# CONN.net
KiCad netlist of a schematic drawn in Altium Designer
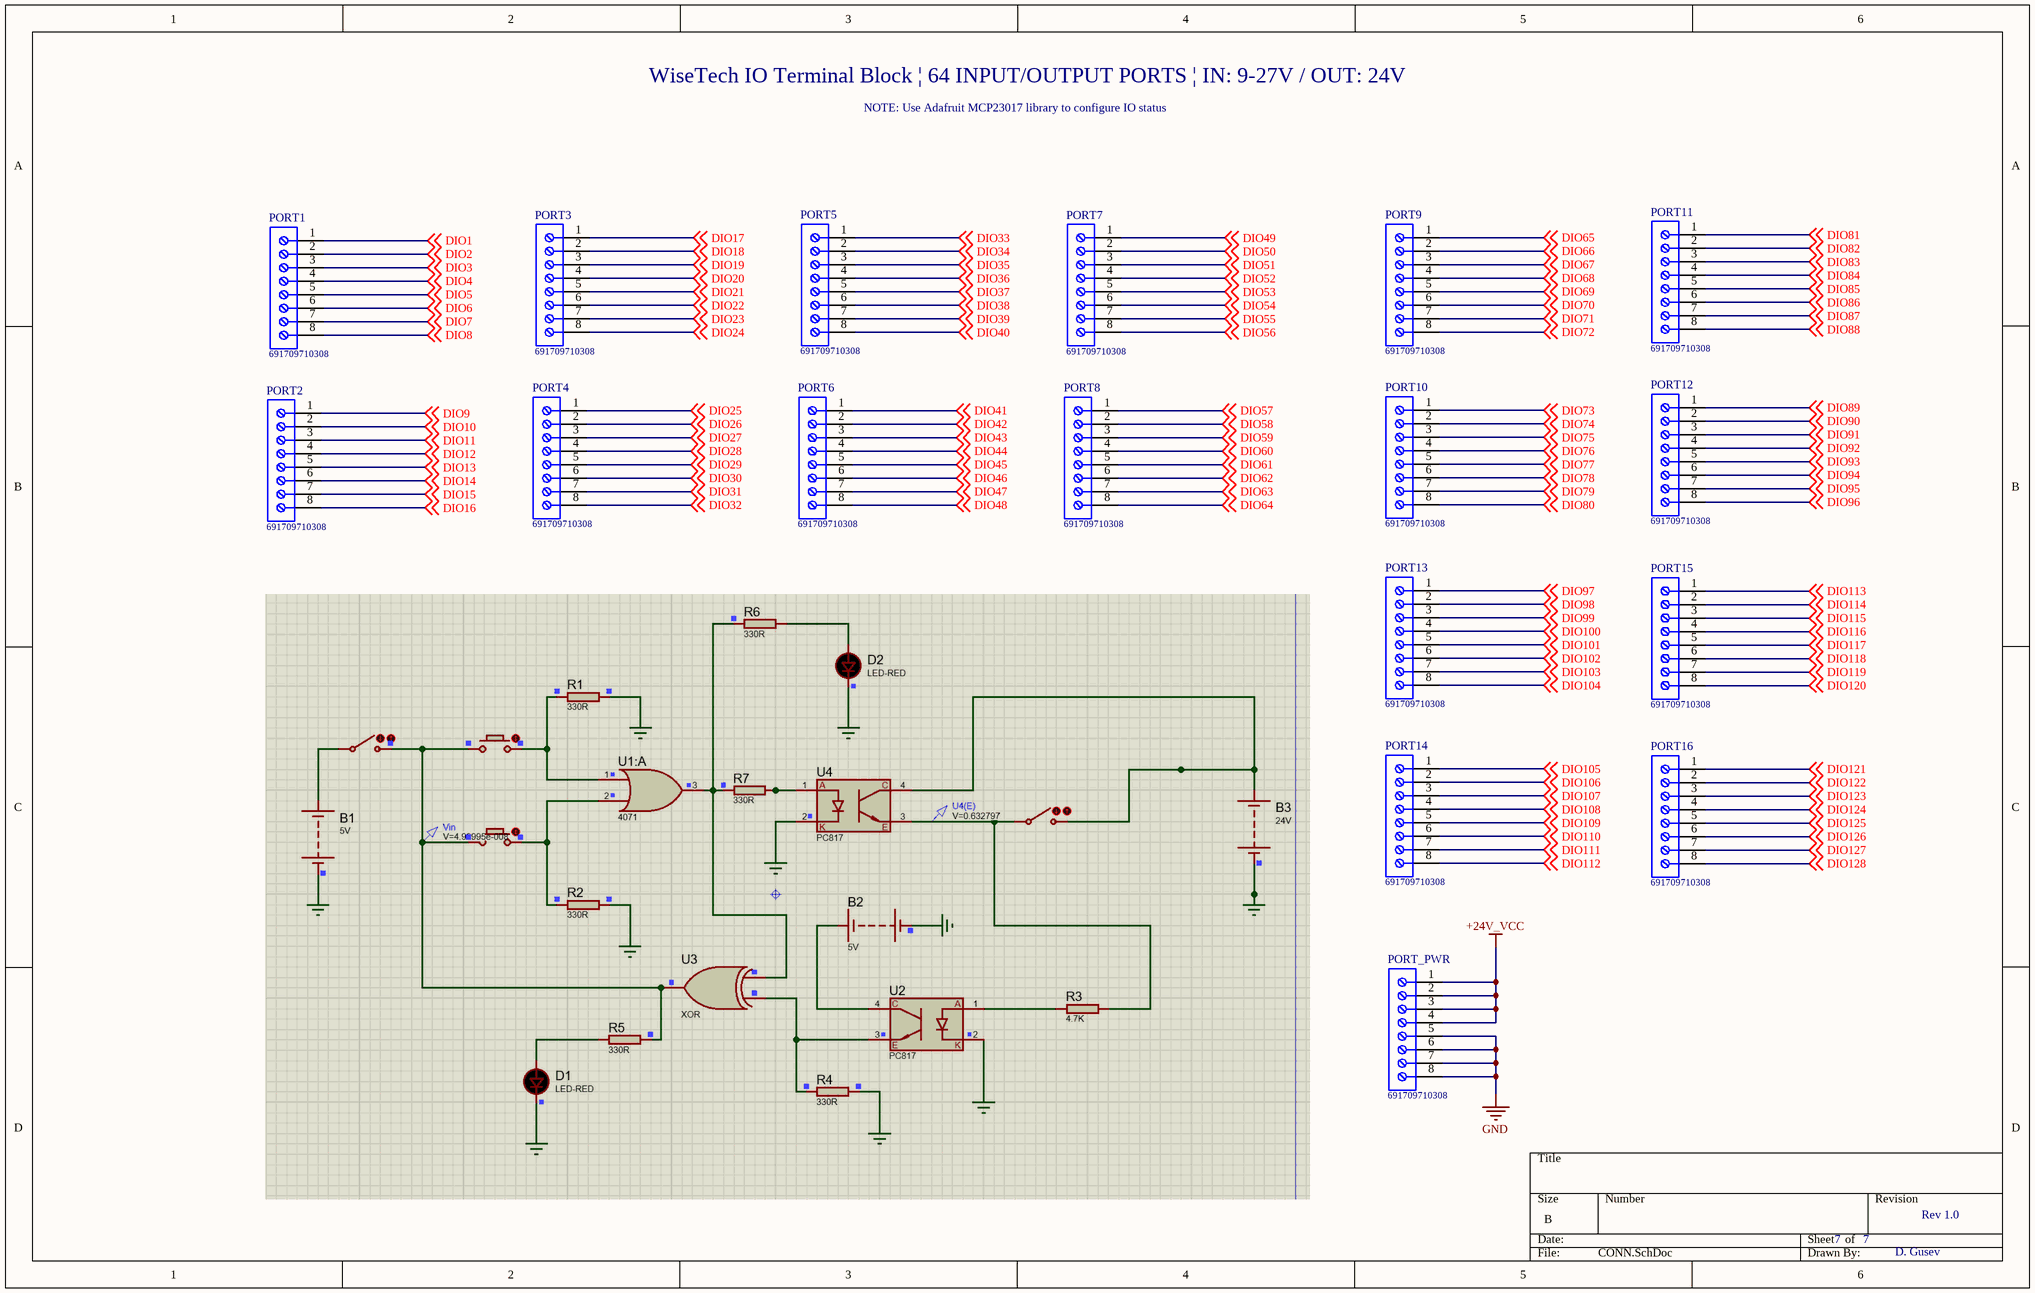
[diagram p0: CONN.SchDoc]

(export (version "E")
  (design (tool "Eeschema 10.0.6"))
  (components
    (comp (ref "PORT1")
      (value "691709710308")
      (footprint "691709710308")
      (description "Serie 7097 - 5.00 mm Horizontal Entry SMT with Pressure Clamp WR-TBL, 8 pin")
      (fields (field (name "MANUFACTURER") "Wurth Elektronik") (field (name "PUBLISHER") "WurthElektronik"))
      (libsource (lib "") (part "WE-CN-1P-F-TB8_2"))
    )
    (comp (ref "PORT2")
      (value "691709710308")
      (footprint "691709710308")
      (description "Serie 7097 - 5.00 mm Horizontal Entry SMT with Pressure Clamp WR-TBL, 8 pin")
      (fields (field (name "MANUFACTURER") "Wurth Elektronik") (field (name "PUBLISHER") "WurthElektronik"))
      (libsource (lib "") (part "WE-CN-1P-F-TB8_2"))
    )
    (comp (ref "PORT3")
      (value "691709710308")
      (footprint "691709710308")
      (description "Serie 7097 - 5.00 mm Horizontal Entry SMT with Pressure Clamp WR-TBL, 8 pin")
      (fields (field (name "MANUFACTURER") "Wurth Elektronik") (field (name "PUBLISHER") "WurthElektronik"))
      (libsource (lib "") (part "WE-CN-1P-F-TB8_2"))
    )
    (comp (ref "PORT4")
      (value "691709710308")
      (footprint "691709710308")
      (description "Serie 7097 - 5.00 mm Horizontal Entry SMT with Pressure Clamp WR-TBL, 8 pin")
      (fields (field (name "MANUFACTURER") "Wurth Elektronik") (field (name "PUBLISHER") "WurthElektronik"))
      (libsource (lib "") (part "WE-CN-1P-F-TB8_2"))
    )
    (comp (ref "PORT5")
      (value "691709710308")
      (footprint "691709710308")
      (description "Serie 7097 - 5.00 mm Horizontal Entry SMT with Pressure Clamp WR-TBL, 8 pin")
      (fields (field (name "MANUFACTURER") "Wurth Elektronik") (field (name "PUBLISHER") "WurthElektronik"))
      (libsource (lib "") (part "WE-CN-1P-F-TB8_3"))
    )
    (comp (ref "PORT6")
      (value "691709710308")
      (footprint "691709710308")
      (description "Serie 7097 - 5.00 mm Horizontal Entry SMT with Pressure Clamp WR-TBL, 8 pin")
      (fields (field (name "MANUFACTURER") "Wurth Elektronik") (field (name "PUBLISHER") "WurthElektronik"))
      (libsource (lib "") (part "WE-CN-1P-F-TB8_3"))
    )
    (comp (ref "PORT7")
      (value "691709710308")
      (footprint "691709710308")
      (description "Serie 7097 - 5.00 mm Horizontal Entry SMT with Pressure Clamp WR-TBL, 8 pin")
      (fields (field (name "MANUFACTURER") "Wurth Elektronik") (field (name "PUBLISHER") "WurthElektronik"))
      (libsource (lib "") (part "WE-CN-1P-F-TB8_3"))
    )
    (comp (ref "PORT8")
      (value "691709710308")
      (footprint "691709710308")
      (description "Serie 7097 - 5.00 mm Horizontal Entry SMT with Pressure Clamp WR-TBL, 8 pin")
      (fields (field (name "MANUFACTURER") "Wurth Elektronik") (field (name "PUBLISHER") "WurthElektronik"))
      (libsource (lib "") (part "WE-CN-1P-F-TB8_3"))
    )
    (comp (ref "PORT9")
      (value "691709710308")
      (footprint "691709710308")
      (description "Serie 7097 - 5.00 mm Horizontal Entry SMT with Pressure Clamp WR-TBL, 8 pin")
      (fields (field (name "MANUFACTURER") "Wurth Elektronik") (field (name "PUBLISHER") "WurthElektronik"))
      (libsource (lib "Altium Content Vault") (part "WE-CN-1P-F-TB8"))
    )
    (comp (ref "PORT10")
      (value "691709710308")
      (footprint "691709710308")
      (description "Serie 7097 - 5.00 mm Horizontal Entry SMT with Pressure Clamp WR-TBL, 8 pin")
      (fields (field (name "MANUFACTURER") "Wurth Elektronik") (field (name "PUBLISHER") "WurthElektronik"))
      (libsource (lib "") (part "WE-CN-1P-F-TB8_1"))
    )
    (comp (ref "PORT11")
      (value "691709710308")
      (footprint "691709710308")
      (description "Serie 7097 - 5.00 mm Horizontal Entry SMT with Pressure Clamp WR-TBL, 8 pin")
      (fields (field (name "MANUFACTURER") "Wurth Elektronik") (field (name "PUBLISHER") "WurthElektronik"))
      (libsource (lib "Altium Content Vault") (part "WE-CN-1P-F-TB8"))
    )
    (comp (ref "PORT12")
      (value "691709710308")
      (footprint "691709710308")
      (description "Serie 7097 - 5.00 mm Horizontal Entry SMT with Pressure Clamp WR-TBL, 8 pin")
      (fields (field (name "MANUFACTURER") "Wurth Elektronik") (field (name "PUBLISHER") "WurthElektronik"))
      (libsource (lib "Altium Content Vault") (part "WE-CN-1P-F-TB8"))
    )
    (comp (ref "PORT13")
      (value "691709710308")
      (footprint "691709710308")
      (description "Serie 7097 - 5.00 mm Horizontal Entry SMT with Pressure Clamp WR-TBL, 8 pin")
      (fields (field (name "MANUFACTURER") "Wurth Elektronik") (field (name "PUBLISHER") "WurthElektronik"))
      (libsource (lib "") (part "WE-CN-1P-F-TB8_1"))
    )
    (comp (ref "PORT14")
      (value "691709710308")
      (footprint "691709710308")
      (description "Serie 7097 - 5.00 mm Horizontal Entry SMT with Pressure Clamp WR-TBL, 8 pin")
      (fields (field (name "MANUFACTURER") "Wurth Elektronik") (field (name "PUBLISHER") "WurthElektronik"))
      (libsource (lib "") (part "WE-CN-1P-F-TB8_1"))
    )
    (comp (ref "PORT15")
      (value "691709710308")
      (footprint "691709710308")
      (description "Serie 7097 - 5.00 mm Horizontal Entry SMT with Pressure Clamp WR-TBL, 8 pin")
      (fields (field (name "MANUFACTURER") "Wurth Elektronik") (field (name "PUBLISHER") "WurthElektronik"))
      (libsource (lib "") (part "WE-CN-1P-F-TB8_1"))
    )
    (comp (ref "PORT16")
      (value "691709710308")
      (footprint "691709710308")
      (description "Serie 7097 - 5.00 mm Horizontal Entry SMT with Pressure Clamp WR-TBL, 8 pin")
      (fields (field (name "MANUFACTURER") "Wurth Elektronik") (field (name "PUBLISHER") "WurthElektronik"))
      (libsource (lib "") (part "WE-CN-1P-F-TB8_1"))
    )
    (comp (ref "PORT_PWR")
      (value "691709710308")
      (footprint "691709710308")
      (description "Serie 7097 - 5.00 mm Horizontal Entry SMT with Pressure Clamp WR-TBL, 8 pin")
      (fields (field (name "MANUFACTURER") "Wurth Elektronik") (field (name "PUBLISHER") "WurthElektronik"))
      (libsource (lib "") (part "WE-CN-1P-F-TB8_1"))
    )
  )
  (nets
    (net (code "1") (name "+24V_VCC") (class "Default")
      (node (ref "PORT_PWR") (pin "1") (pinfunction "1_1") (pintype "passive"))
      (node (ref "PORT_PWR") (pin "2") (pinfunction "2_2") (pintype "passive"))
      (node (ref "PORT_PWR") (pin "3") (pinfunction "3_3") (pintype "passive"))
      (node (ref "PORT_PWR") (pin "4") (pinfunction "4_4") (pintype "passive"))
    )
    (net (code "2") (name "DIO1") (class "Default")
      (node (ref "PORT1") (pin "1") (pinfunction "1_1") (pintype "passive"))
    )
    (net (code "3") (name "DIO2") (class "Default")
      (node (ref "PORT1") (pin "2") (pinfunction "2_2") (pintype "passive"))
    )
    (net (code "4") (name "DIO3") (class "Default")
      (node (ref "PORT1") (pin "3") (pinfunction "3_3") (pintype "passive"))
    )
    (net (code "5") (name "DIO4") (class "Default")
      (node (ref "PORT1") (pin "4") (pinfunction "4_4") (pintype "passive"))
    )
    (net (code "6") (name "DIO5") (class "Default")
      (node (ref "PORT1") (pin "5") (pinfunction "5_5") (pintype "passive"))
    )
    (net (code "7") (name "DIO6") (class "Default")
      (node (ref "PORT1") (pin "6") (pinfunction "6_6") (pintype "passive"))
    )
    (net (code "8") (name "DIO7") (class "Default")
      (node (ref "PORT1") (pin "7") (pinfunction "7_7") (pintype "passive"))
    )
    (net (code "9") (name "DIO8") (class "Default")
      (node (ref "PORT1") (pin "8") (pinfunction "8_8") (pintype "passive"))
    )
    (net (code "10") (name "DIO9") (class "Default")
      (node (ref "PORT2") (pin "1") (pinfunction "1_1") (pintype "passive"))
    )
    (net (code "11") (name "DIO10") (class "Default")
      (node (ref "PORT2") (pin "2") (pinfunction "2_2") (pintype "passive"))
    )
    (net (code "12") (name "DIO11") (class "Default")
      (node (ref "PORT2") (pin "3") (pinfunction "3_3") (pintype "passive"))
    )
    (net (code "13") (name "DIO12") (class "Default")
      (node (ref "PORT2") (pin "4") (pinfunction "4_4") (pintype "passive"))
    )
    (net (code "14") (name "DIO13") (class "Default")
      (node (ref "PORT2") (pin "5") (pinfunction "5_5") (pintype "passive"))
    )
    (net (code "15") (name "DIO14") (class "Default")
      (node (ref "PORT2") (pin "6") (pinfunction "6_6") (pintype "passive"))
    )
    (net (code "16") (name "DIO15") (class "Default")
      (node (ref "PORT2") (pin "7") (pinfunction "7_7") (pintype "passive"))
    )
    (net (code "17") (name "DIO16") (class "Default")
      (node (ref "PORT2") (pin "8") (pinfunction "8_8") (pintype "passive"))
    )
    (net (code "18") (name "DIO17") (class "Default")
      (node (ref "PORT3") (pin "1") (pinfunction "1_1") (pintype "passive"))
    )
    (net (code "19") (name "DIO18") (class "Default")
      (node (ref "PORT3") (pin "2") (pinfunction "2_2") (pintype "passive"))
    )
    (net (code "20") (name "DIO19") (class "Default")
      (node (ref "PORT3") (pin "3") (pinfunction "3_3") (pintype "passive"))
    )
    (net (code "21") (name "DIO20") (class "Default")
      (node (ref "PORT3") (pin "4") (pinfunction "4_4") (pintype "passive"))
    )
    (net (code "22") (name "DIO21") (class "Default")
      (node (ref "PORT3") (pin "5") (pinfunction "5_5") (pintype "passive"))
    )
    (net (code "23") (name "DIO22") (class "Default")
      (node (ref "PORT3") (pin "6") (pinfunction "6_6") (pintype "passive"))
    )
    (net (code "24") (name "DIO23") (class "Default")
      (node (ref "PORT3") (pin "7") (pinfunction "7_7") (pintype "passive"))
    )
    (net (code "25") (name "DIO24") (class "Default")
      (node (ref "PORT3") (pin "8") (pinfunction "8_8") (pintype "passive"))
    )
    (net (code "26") (name "DIO25") (class "Default")
      (node (ref "PORT4") (pin "1") (pinfunction "1_1") (pintype "passive"))
    )
    (net (code "27") (name "DIO26") (class "Default")
      (node (ref "PORT4") (pin "2") (pinfunction "2_2") (pintype "passive"))
    )
    (net (code "28") (name "DIO27") (class "Default")
      (node (ref "PORT4") (pin "3") (pinfunction "3_3") (pintype "passive"))
    )
    (net (code "29") (name "DIO28") (class "Default")
      (node (ref "PORT4") (pin "4") (pinfunction "4_4") (pintype "passive"))
    )
    (net (code "30") (name "DIO29") (class "Default")
      (node (ref "PORT4") (pin "5") (pinfunction "5_5") (pintype "passive"))
    )
    (net (code "31") (name "DIO30") (class "Default")
      (node (ref "PORT4") (pin "6") (pinfunction "6_6") (pintype "passive"))
    )
    (net (code "32") (name "DIO31") (class "Default")
      (node (ref "PORT4") (pin "7") (pinfunction "7_7") (pintype "passive"))
    )
    (net (code "33") (name "DIO32") (class "Default")
      (node (ref "PORT4") (pin "8") (pinfunction "8_8") (pintype "passive"))
    )
    (net (code "34") (name "DIO33") (class "Default")
      (node (ref "PORT5") (pin "1") (pinfunction "1_1") (pintype "passive"))
    )
    (net (code "35") (name "DIO34") (class "Default")
      (node (ref "PORT5") (pin "2") (pinfunction "2_2") (pintype "passive"))
    )
    (net (code "36") (name "DIO35") (class "Default")
      (node (ref "PORT5") (pin "3") (pinfunction "3_3") (pintype "passive"))
    )
    (net (code "37") (name "DIO36") (class "Default")
      (node (ref "PORT5") (pin "4") (pinfunction "4_4") (pintype "passive"))
    )
    (net (code "38") (name "DIO37") (class "Default")
      (node (ref "PORT5") (pin "5") (pinfunction "5_5") (pintype "passive"))
    )
    (net (code "39") (name "DIO38") (class "Default")
      (node (ref "PORT5") (pin "6") (pinfunction "6_6") (pintype "passive"))
    )
    (net (code "40") (name "DIO39") (class "Default")
      (node (ref "PORT5") (pin "7") (pinfunction "7_7") (pintype "passive"))
    )
    (net (code "41") (name "DIO40") (class "Default")
      (node (ref "PORT5") (pin "8") (pinfunction "8_8") (pintype "passive"))
    )
    (net (code "42") (name "DIO41") (class "Default")
      (node (ref "PORT6") (pin "1") (pinfunction "1_1") (pintype "passive"))
    )
    (net (code "43") (name "DIO42") (class "Default")
      (node (ref "PORT6") (pin "2") (pinfunction "2_2") (pintype "passive"))
    )
    (net (code "44") (name "DIO43") (class "Default")
      (node (ref "PORT6") (pin "3") (pinfunction "3_3") (pintype "passive"))
    )
    (net (code "45") (name "DIO44") (class "Default")
      (node (ref "PORT6") (pin "4") (pinfunction "4_4") (pintype "passive"))
    )
    (net (code "46") (name "DIO45") (class "Default")
      (node (ref "PORT6") (pin "5") (pinfunction "5_5") (pintype "passive"))
    )
    (net (code "47") (name "DIO46") (class "Default")
      (node (ref "PORT6") (pin "6") (pinfunction "6_6") (pintype "passive"))
    )
    (net (code "48") (name "DIO47") (class "Default")
      (node (ref "PORT6") (pin "7") (pinfunction "7_7") (pintype "passive"))
    )
    (net (code "49") (name "DIO48") (class "Default")
      (node (ref "PORT6") (pin "8") (pinfunction "8_8") (pintype "passive"))
    )
    (net (code "50") (name "DIO49") (class "Default")
      (node (ref "PORT7") (pin "1") (pinfunction "1_1") (pintype "passive"))
    )
    (net (code "51") (name "DIO50") (class "Default")
      (node (ref "PORT7") (pin "2") (pinfunction "2_2") (pintype "passive"))
    )
    (net (code "52") (name "DIO51") (class "Default")
      (node (ref "PORT7") (pin "3") (pinfunction "3_3") (pintype "passive"))
    )
    (net (code "53") (name "DIO52") (class "Default")
      (node (ref "PORT7") (pin "4") (pinfunction "4_4") (pintype "passive"))
    )
    (net (code "54") (name "DIO53") (class "Default")
      (node (ref "PORT7") (pin "5") (pinfunction "5_5") (pintype "passive"))
    )
    (net (code "55") (name "DIO54") (class "Default")
      (node (ref "PORT7") (pin "6") (pinfunction "6_6") (pintype "passive"))
    )
    (net (code "56") (name "DIO55") (class "Default")
      (node (ref "PORT7") (pin "7") (pinfunction "7_7") (pintype "passive"))
    )
    (net (code "57") (name "DIO56") (class "Default")
      (node (ref "PORT7") (pin "8") (pinfunction "8_8") (pintype "passive"))
    )
    (net (code "58") (name "DIO57") (class "Default")
      (node (ref "PORT8") (pin "1") (pinfunction "1_1") (pintype "passive"))
    )
    (net (code "59") (name "DIO58") (class "Default")
      (node (ref "PORT8") (pin "2") (pinfunction "2_2") (pintype "passive"))
    )
    (net (code "60") (name "DIO59") (class "Default")
      (node (ref "PORT8") (pin "3") (pinfunction "3_3") (pintype "passive"))
    )
    (net (code "61") (name "DIO60") (class "Default")
      (node (ref "PORT8") (pin "4") (pinfunction "4_4") (pintype "passive"))
    )
    (net (code "62") (name "DIO61") (class "Default")
      (node (ref "PORT8") (pin "5") (pinfunction "5_5") (pintype "passive"))
    )
    (net (code "63") (name "DIO62") (class "Default")
      (node (ref "PORT8") (pin "6") (pinfunction "6_6") (pintype "passive"))
    )
    (net (code "64") (name "DIO63") (class "Default")
      (node (ref "PORT8") (pin "7") (pinfunction "7_7") (pintype "passive"))
    )
    (net (code "65") (name "DIO64") (class "Default")
      (node (ref "PORT8") (pin "8") (pinfunction "8_8") (pintype "passive"))
    )
    (net (code "66") (name "DIO65") (class "Default")
      (node (ref "PORT9") (pin "1") (pinfunction "1_1") (pintype "passive"))
    )
    (net (code "67") (name "DIO66") (class "Default")
      (node (ref "PORT9") (pin "2") (pinfunction "2_2") (pintype "passive"))
    )
    (net (code "68") (name "DIO67") (class "Default")
      (node (ref "PORT9") (pin "3") (pinfunction "3_3") (pintype "passive"))
    )
    (net (code "69") (name "DIO68") (class "Default")
      (node (ref "PORT9") (pin "4") (pinfunction "4_4") (pintype "passive"))
    )
    (net (code "70") (name "DIO69") (class "Default")
      (node (ref "PORT9") (pin "5") (pinfunction "5_5") (pintype "passive"))
    )
    (net (code "71") (name "DIO70") (class "Default")
      (node (ref "PORT9") (pin "6") (pinfunction "6_6") (pintype "passive"))
    )
    (net (code "72") (name "DIO71") (class "Default")
      (node (ref "PORT9") (pin "7") (pinfunction "7_7") (pintype "passive"))
    )
    (net (code "73") (name "DIO72") (class "Default")
      (node (ref "PORT9") (pin "8") (pinfunction "8_8") (pintype "passive"))
    )
    (net (code "74") (name "DIO73") (class "Default")
      (node (ref "PORT10") (pin "1") (pinfunction "1_1") (pintype "passive"))
    )
    (net (code "75") (name "DIO74") (class "Default")
      (node (ref "PORT10") (pin "2") (pinfunction "2_2") (pintype "passive"))
    )
    (net (code "76") (name "DIO75") (class "Default")
      (node (ref "PORT10") (pin "3") (pinfunction "3_3") (pintype "passive"))
    )
    (net (code "77") (name "DIO76") (class "Default")
      (node (ref "PORT10") (pin "4") (pinfunction "4_4") (pintype "passive"))
    )
    (net (code "78") (name "DIO77") (class "Default")
      (node (ref "PORT10") (pin "5") (pinfunction "5_5") (pintype "passive"))
    )
    (net (code "79") (name "DIO78") (class "Default")
      (node (ref "PORT10") (pin "6") (pinfunction "6_6") (pintype "passive"))
    )
    (net (code "80") (name "DIO79") (class "Default")
      (node (ref "PORT10") (pin "7") (pinfunction "7_7") (pintype "passive"))
    )
    (net (code "81") (name "DIO80") (class "Default")
      (node (ref "PORT10") (pin "8") (pinfunction "8_8") (pintype "passive"))
    )
    (net (code "82") (name "DIO81") (class "Default")
      (node (ref "PORT11") (pin "1") (pinfunction "1_1") (pintype "passive"))
    )
    (net (code "83") (name "DIO82") (class "Default")
      (node (ref "PORT11") (pin "2") (pinfunction "2_2") (pintype "passive"))
    )
    (net (code "84") (name "DIO83") (class "Default")
      (node (ref "PORT11") (pin "3") (pinfunction "3_3") (pintype "passive"))
    )
    (net (code "85") (name "DIO84") (class "Default")
      (node (ref "PORT11") (pin "4") (pinfunction "4_4") (pintype "passive"))
    )
    (net (code "86") (name "DIO85") (class "Default")
      (node (ref "PORT11") (pin "5") (pinfunction "5_5") (pintype "passive"))
    )
    (net (code "87") (name "DIO86") (class "Default")
      (node (ref "PORT11") (pin "6") (pinfunction "6_6") (pintype "passive"))
    )
    (net (code "88") (name "DIO87") (class "Default")
      (node (ref "PORT11") (pin "7") (pinfunction "7_7") (pintype "passive"))
    )
    (net (code "89") (name "DIO88") (class "Default")
      (node (ref "PORT11") (pin "8") (pinfunction "8_8") (pintype "passive"))
    )
    (net (code "90") (name "DIO89") (class "Default")
      (node (ref "PORT12") (pin "1") (pinfunction "1_1") (pintype "passive"))
    )
    (net (code "91") (name "DIO90") (class "Default")
      (node (ref "PORT12") (pin "2") (pinfunction "2_2") (pintype "passive"))
    )
    (net (code "92") (name "DIO91") (class "Default")
      (node (ref "PORT12") (pin "3") (pinfunction "3_3") (pintype "passive"))
    )
    (net (code "93") (name "DIO92") (class "Default")
      (node (ref "PORT12") (pin "4") (pinfunction "4_4") (pintype "passive"))
    )
    (net (code "94") (name "DIO93") (class "Default")
      (node (ref "PORT12") (pin "5") (pinfunction "5_5") (pintype "passive"))
    )
    (net (code "95") (name "DIO94") (class "Default")
      (node (ref "PORT12") (pin "6") (pinfunction "6_6") (pintype "passive"))
    )
    (net (code "96") (name "DIO95") (class "Default")
      (node (ref "PORT12") (pin "7") (pinfunction "7_7") (pintype "passive"))
    )
    (net (code "97") (name "DIO96") (class "Default")
      (node (ref "PORT12") (pin "8") (pinfunction "8_8") (pintype "passive"))
    )
    (net (code "98") (name "DIO97") (class "Default")
      (node (ref "PORT13") (pin "1") (pinfunction "1_1") (pintype "passive"))
    )
    (net (code "99") (name "DIO98") (class "Default")
      (node (ref "PORT13") (pin "2") (pinfunction "2_2") (pintype "passive"))
    )
    (net (code "100") (name "DIO99") (class "Default")
      (node (ref "PORT13") (pin "3") (pinfunction "3_3") (pintype "passive"))
    )
    (net (code "101") (name "DIO100") (class "Default")
      (node (ref "PORT13") (pin "4") (pinfunction "4_4") (pintype "passive"))
    )
    (net (code "102") (name "DIO101") (class "Default")
      (node (ref "PORT13") (pin "5") (pinfunction "5_5") (pintype "passive"))
    )
    (net (code "103") (name "DIO102") (class "Default")
      (node (ref "PORT13") (pin "6") (pinfunction "6_6") (pintype "passive"))
    )
    (net (code "104") (name "DIO103") (class "Default")
      (node (ref "PORT13") (pin "7") (pinfunction "7_7") (pintype "passive"))
    )
    (net (code "105") (name "DIO104") (class "Default")
      (node (ref "PORT13") (pin "8") (pinfunction "8_8") (pintype "passive"))
    )
    (net (code "106") (name "DIO105") (class "Default")
      (node (ref "PORT14") (pin "1") (pinfunction "1_1") (pintype "passive"))
    )
    (net (code "107") (name "DIO106") (class "Default")
      (node (ref "PORT14") (pin "2") (pinfunction "2_2") (pintype "passive"))
    )
    (net (code "108") (name "DIO107") (class "Default")
      (node (ref "PORT14") (pin "3") (pinfunction "3_3") (pintype "passive"))
    )
    (net (code "109") (name "DIO108") (class "Default")
      (node (ref "PORT14") (pin "4") (pinfunction "4_4") (pintype "passive"))
    )
    (net (code "110") (name "DIO109") (class "Default")
      (node (ref "PORT14") (pin "5") (pinfunction "5_5") (pintype "passive"))
    )
    (net (code "111") (name "DIO110") (class "Default")
      (node (ref "PORT14") (pin "6") (pinfunction "6_6") (pintype "passive"))
    )
    (net (code "112") (name "DIO111") (class "Default")
      (node (ref "PORT14") (pin "7") (pinfunction "7_7") (pintype "passive"))
    )
    (net (code "113") (name "DIO112") (class "Default")
      (node (ref "PORT14") (pin "8") (pinfunction "8_8") (pintype "passive"))
    )
    (net (code "114") (name "DIO113") (class "Default")
      (node (ref "PORT15") (pin "1") (pinfunction "1_1") (pintype "passive"))
    )
    (net (code "115") (name "DIO114") (class "Default")
      (node (ref "PORT15") (pin "2") (pinfunction "2_2") (pintype "passive"))
    )
    (net (code "116") (name "DIO115") (class "Default")
      (node (ref "PORT15") (pin "3") (pinfunction "3_3") (pintype "passive"))
    )
    (net (code "117") (name "DIO116") (class "Default")
      (node (ref "PORT15") (pin "4") (pinfunction "4_4") (pintype "passive"))
    )
    (net (code "118") (name "DIO117") (class "Default")
      (node (ref "PORT15") (pin "5") (pinfunction "5_5") (pintype "passive"))
    )
    (net (code "119") (name "DIO118") (class "Default")
      (node (ref "PORT15") (pin "6") (pinfunction "6_6") (pintype "passive"))
    )
    (net (code "120") (name "DIO119") (class "Default")
      (node (ref "PORT15") (pin "7") (pinfunction "7_7") (pintype "passive"))
    )
    (net (code "121") (name "DIO120") (class "Default")
      (node (ref "PORT15") (pin "8") (pinfunction "8_8") (pintype "passive"))
    )
    (net (code "122") (name "DIO121") (class "Default")
      (node (ref "PORT16") (pin "1") (pinfunction "1_1") (pintype "passive"))
    )
    (net (code "123") (name "DIO122") (class "Default")
      (node (ref "PORT16") (pin "2") (pinfunction "2_2") (pintype "passive"))
    )
    (net (code "124") (name "DIO123") (class "Default")
      (node (ref "PORT16") (pin "3") (pinfunction "3_3") (pintype "passive"))
    )
    (net (code "125") (name "DIO124") (class "Default")
      (node (ref "PORT16") (pin "4") (pinfunction "4_4") (pintype "passive"))
    )
    (net (code "126") (name "DIO125") (class "Default")
      (node (ref "PORT16") (pin "5") (pinfunction "5_5") (pintype "passive"))
    )
    (net (code "127") (name "DIO126") (class "Default")
      (node (ref "PORT16") (pin "6") (pinfunction "6_6") (pintype "passive"))
    )
    (net (code "128") (name "DIO127") (class "Default")
      (node (ref "PORT16") (pin "7") (pinfunction "7_7") (pintype "passive"))
    )
    (net (code "129") (name "DIO128") (class "Default")
      (node (ref "PORT16") (pin "8") (pinfunction "8_8") (pintype "passive"))
    )
    (net (code "130") (name "GND") (class "Default")
      (node (ref "PORT_PWR") (pin "5") (pinfunction "5_5") (pintype "passive"))
      (node (ref "PORT_PWR") (pin "6") (pinfunction "6_6") (pintype "passive"))
      (node (ref "PORT_PWR") (pin "7") (pinfunction "7_7") (pintype "passive"))
      (node (ref "PORT_PWR") (pin "8") (pinfunction "8_8") (pintype "passive"))
    )
  )
)
